# Radio.net
KiCad netlist of a schematic drawn in EAGLE
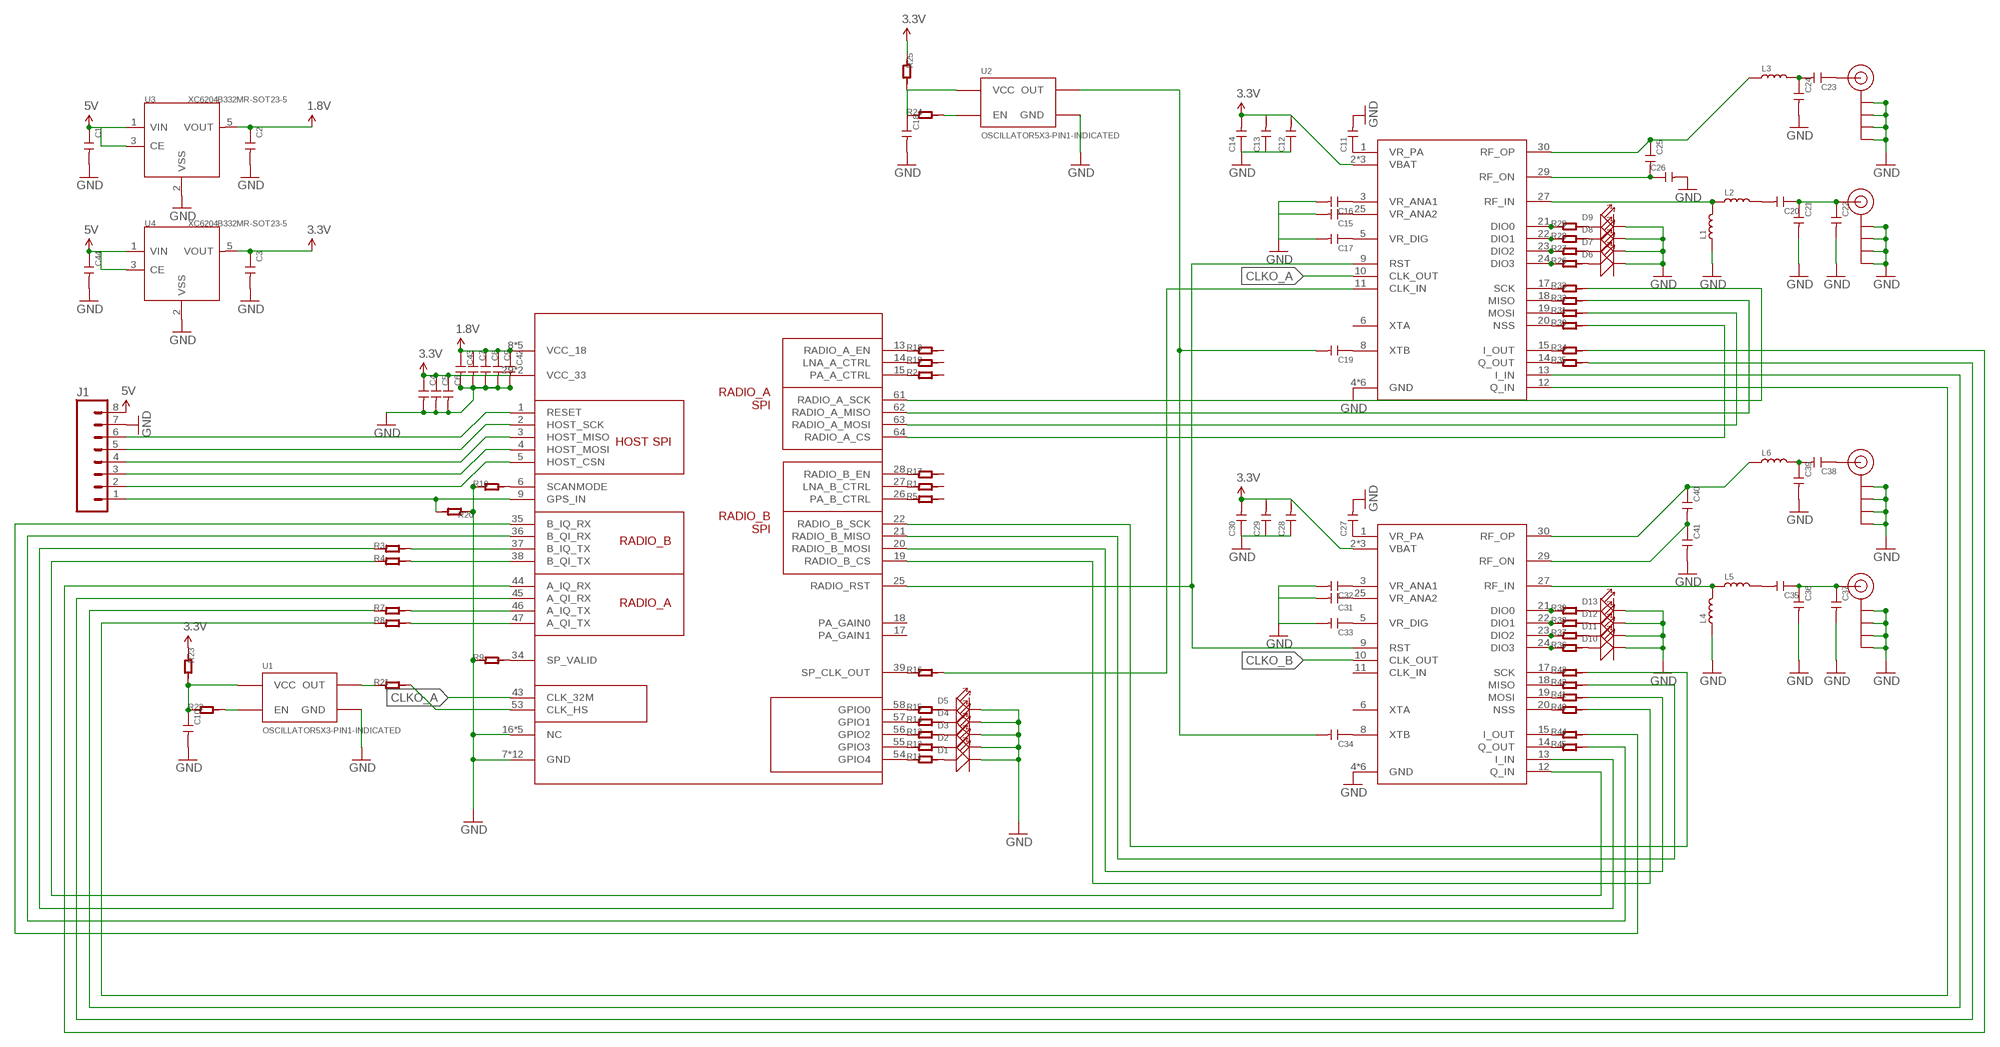
[diagram p0: schematic, sheet 1]

(export (version "E")
  (design (tool "Eeschema 10.0.6"))
  (components
    (comp (ref "C1")
      (value "CAP-0603")
      (footprint "eagle-import:C0603")
      (libsource (lib "eagle-import") (part "CAP-0603"))
    )
    (comp (ref "C2")
      (value "CAP-0402")
      (footprint "eagle-import:C0402")
      (libsource (lib "eagle-import") (part "CAP-0402"))
    )
    (comp (ref "C3")
      (value "CAP-0603")
      (footprint "eagle-import:C0603")
      (libsource (lib "eagle-import") (part "CAP-0603"))
    )
    (comp (ref "C4")
      (value "CAP-0402")
      (footprint "eagle-import:C0402")
      (libsource (lib "eagle-import") (part "CAP-0402"))
    )
    (comp (ref "C5")
      (value "CAP-0805")
      (footprint "eagle-import:C0805")
      (libsource (lib "eagle-import") (part "CAP-0805"))
    )
    (comp (ref "C6")
      (value "CAP-0402")
      (footprint "eagle-import:C0402")
      (libsource (lib "eagle-import") (part "CAP-0402"))
    )
    (comp (ref "C7")
      (value "CAP-0402")
      (footprint "eagle-import:C0402")
      (libsource (lib "eagle-import") (part "CAP-0402"))
    )
    (comp (ref "C8")
      (value "CAP-0402")
      (footprint "eagle-import:C0402")
      (libsource (lib "eagle-import") (part "CAP-0402"))
    )
    (comp (ref "C9")
      (value "CAP-0402")
      (footprint "eagle-import:C0402")
      (libsource (lib "eagle-import") (part "CAP-0402"))
    )
    (comp (ref "C10")
      (value "CAP-0402")
      (footprint "eagle-import:C0402")
      (libsource (lib "eagle-import") (part "CAP-0402"))
    )
    (comp (ref "C11")
      (value "CAP-0402")
      (footprint "eagle-import:C0402")
      (libsource (lib "eagle-import") (part "CAP-0402"))
    )
    (comp (ref "C12")
      (value "CAP-0402")
      (footprint "eagle-import:C0402")
      (libsource (lib "eagle-import") (part "CAP-0402"))
    )
    (comp (ref "C13")
      (value "CAP-0402")
      (footprint "eagle-import:C0402")
      (libsource (lib "eagle-import") (part "CAP-0402"))
    )
    (comp (ref "C14")
      (value "CAP-0402")
      (footprint "eagle-import:C0402")
      (libsource (lib "eagle-import") (part "CAP-0402"))
    )
    (comp (ref "C15")
      (value "CAP-0402")
      (footprint "eagle-import:C0402")
      (libsource (lib "eagle-import") (part "CAP-0402"))
    )
    (comp (ref "C16")
      (value "CAP-0402")
      (footprint "eagle-import:C0402")
      (libsource (lib "eagle-import") (part "CAP-0402"))
    )
    (comp (ref "C17")
      (value "CAP-0402")
      (footprint "eagle-import:C0402")
      (libsource (lib "eagle-import") (part "CAP-0402"))
    )
    (comp (ref "C18")
      (value "CAP-0402")
      (footprint "eagle-import:C0402")
      (libsource (lib "eagle-import") (part "CAP-0402"))
    )
    (comp (ref "C19")
      (value "CAP-0402")
      (footprint "eagle-import:C0402")
      (libsource (lib "eagle-import") (part "CAP-0402"))
    )
    (comp (ref "C20")
      (value "CAP-0402")
      (footprint "eagle-import:C0402")
      (libsource (lib "eagle-import") (part "CAP-0402"))
    )
    (comp (ref "C21")
      (value "CAP-0402")
      (footprint "eagle-import:C0402")
      (libsource (lib "eagle-import") (part "CAP-0402"))
    )
    (comp (ref "C22")
      (value "CAP-0402")
      (footprint "eagle-import:C0402")
      (libsource (lib "eagle-import") (part "CAP-0402"))
    )
    (comp (ref "C23")
      (value "CAP-0402")
      (footprint "eagle-import:C0402")
      (libsource (lib "eagle-import") (part "CAP-0402"))
    )
    (comp (ref "C24")
      (value "CAP-0402")
      (footprint "eagle-import:C0402")
      (libsource (lib "eagle-import") (part "CAP-0402"))
    )
    (comp (ref "C25")
      (value "CAP-0402")
      (footprint "eagle-import:C0402")
      (libsource (lib "eagle-import") (part "CAP-0402"))
    )
    (comp (ref "C26")
      (value "CAP-0402")
      (footprint "eagle-import:C0402")
      (libsource (lib "eagle-import") (part "CAP-0402"))
    )
    (comp (ref "C27")
      (value "CAP-0402")
      (footprint "eagle-import:C0402")
      (libsource (lib "eagle-import") (part "CAP-0402"))
    )
    (comp (ref "C28")
      (value "CAP-0402")
      (footprint "eagle-import:C0402")
      (libsource (lib "eagle-import") (part "CAP-0402"))
    )
    (comp (ref "C29")
      (value "CAP-0402")
      (footprint "eagle-import:C0402")
      (libsource (lib "eagle-import") (part "CAP-0402"))
    )
    (comp (ref "C30")
      (value "CAP-0402")
      (footprint "eagle-import:C0402")
      (libsource (lib "eagle-import") (part "CAP-0402"))
    )
    (comp (ref "C31")
      (value "CAP-0402")
      (footprint "eagle-import:C0402")
      (libsource (lib "eagle-import") (part "CAP-0402"))
    )
    (comp (ref "C32")
      (value "CAP-0402")
      (footprint "eagle-import:C0402")
      (libsource (lib "eagle-import") (part "CAP-0402"))
    )
    (comp (ref "C33")
      (value "CAP-0402")
      (footprint "eagle-import:C0402")
      (libsource (lib "eagle-import") (part "CAP-0402"))
    )
    (comp (ref "C34")
      (value "CAP-0402")
      (footprint "eagle-import:C0402")
      (libsource (lib "eagle-import") (part "CAP-0402"))
    )
    (comp (ref "C35")
      (value "CAP-0402")
      (footprint "eagle-import:C0402")
      (libsource (lib "eagle-import") (part "CAP-0402"))
    )
    (comp (ref "C36")
      (value "CAP-0402")
      (footprint "eagle-import:C0402")
      (libsource (lib "eagle-import") (part "CAP-0402"))
    )
    (comp (ref "C37")
      (value "CAP-0402")
      (footprint "eagle-import:C0402")
      (libsource (lib "eagle-import") (part "CAP-0402"))
    )
    (comp (ref "C38")
      (value "CAP-0402")
      (footprint "eagle-import:C0402")
      (libsource (lib "eagle-import") (part "CAP-0402"))
    )
    (comp (ref "C39")
      (value "CAP-0402")
      (footprint "eagle-import:C0402")
      (libsource (lib "eagle-import") (part "CAP-0402"))
    )
    (comp (ref "C40")
      (value "CAP-0402")
      (footprint "eagle-import:C0402")
      (libsource (lib "eagle-import") (part "CAP-0402"))
    )
    (comp (ref "C41")
      (value "CAP-0402")
      (footprint "eagle-import:C0402")
      (libsource (lib "eagle-import") (part "CAP-0402"))
    )
    (comp (ref "C42")
      (value "CAP-0402")
      (footprint "eagle-import:C0402")
      (libsource (lib "eagle-import") (part "CAP-0402"))
    )
    (comp (ref "C43")
      (value "CAP-0402")
      (footprint "eagle-import:C0402")
      (libsource (lib "eagle-import") (part "CAP-0402"))
    )
    (comp (ref "C44")
      (value "CAP-0402")
      (footprint "eagle-import:C0402")
      (libsource (lib "eagle-import") (part "CAP-0402"))
    )
    (comp (ref "D1")
      (value "LED-0402")
      (footprint "eagle-import:LED-0402")
      (libsource (lib "eagle-import") (part "LED-0402"))
    )
    (comp (ref "D2")
      (value "LED-0402")
      (footprint "eagle-import:LED-0402")
      (libsource (lib "eagle-import") (part "LED-0402"))
    )
    (comp (ref "D3")
      (value "LED-0402")
      (footprint "eagle-import:LED-0402")
      (libsource (lib "eagle-import") (part "LED-0402"))
    )
    (comp (ref "D4")
      (value "LED-0402")
      (footprint "eagle-import:LED-0402")
      (libsource (lib "eagle-import") (part "LED-0402"))
    )
    (comp (ref "D5")
      (value "LED-0402")
      (footprint "eagle-import:LED-0402")
      (libsource (lib "eagle-import") (part "LED-0402"))
    )
    (comp (ref "D6")
      (value "LED-0402")
      (footprint "eagle-import:LED-0402")
      (libsource (lib "eagle-import") (part "LED-0402"))
    )
    (comp (ref "D7")
      (value "LED-0402")
      (footprint "eagle-import:LED-0402")
      (libsource (lib "eagle-import") (part "LED-0402"))
    )
    (comp (ref "D8")
      (value "LED-0402")
      (footprint "eagle-import:LED-0402")
      (libsource (lib "eagle-import") (part "LED-0402"))
    )
    (comp (ref "D9")
      (value "LED-0402")
      (footprint "eagle-import:LED-0402")
      (libsource (lib "eagle-import") (part "LED-0402"))
    )
    (comp (ref "D10")
      (value "LED-0402")
      (footprint "eagle-import:LED-0402")
      (libsource (lib "eagle-import") (part "LED-0402"))
    )
    (comp (ref "D11")
      (value "LED-0402")
      (footprint "eagle-import:LED-0402")
      (libsource (lib "eagle-import") (part "LED-0402"))
    )
    (comp (ref "D12")
      (value "LED-0402")
      (footprint "eagle-import:LED-0402")
      (libsource (lib "eagle-import") (part "LED-0402"))
    )
    (comp (ref "D13")
      (value "LED-0402")
      (footprint "eagle-import:LED-0402")
      (libsource (lib "eagle-import") (part "LED-0402"))
    )
    (comp (ref "J$1")
      (value "SMA_EDGE")
      (footprint "eagle-import:SMA-EDGE")
      (libsource (lib "eagle-import") (part "SMA_EDGE"))
    )
    (comp (ref "J$2")
      (value "SMA_EDGE")
      (footprint "eagle-import:SMA-EDGE")
      (libsource (lib "eagle-import") (part "SMA_EDGE"))
    )
    (comp (ref "J$3")
      (value "SMA_EDGE")
      (footprint "eagle-import:SMA-EDGE")
      (libsource (lib "eagle-import") (part "SMA_EDGE"))
    )
    (comp (ref "J$4")
      (value "SMA_EDGE")
      (footprint "eagle-import:SMA-EDGE")
      (libsource (lib "eagle-import") (part "SMA_EDGE"))
    )
    (comp (ref "J1")
      (value "M08LOCK")
      (footprint "eagle-import:1X08_LOCK")
      (libsource (lib "eagle-import") (part "M08LOCK"))
    )
    (comp (ref "L1")
      (value "INDUCTOR/FERRITE-BEAD-0402")
      (footprint "eagle-import:L0402")
      (libsource (lib "eagle-import") (part "INDUCTOR/FERRITE-BEAD-0402"))
    )
    (comp (ref "L2")
      (value "INDUCTOR/FERRITE-BEAD-0402")
      (footprint "eagle-import:L0402")
      (libsource (lib "eagle-import") (part "INDUCTOR/FERRITE-BEAD-0402"))
    )
    (comp (ref "L3")
      (value "INDUCTOR/FERRITE-BEAD-0402")
      (footprint "eagle-import:L0402")
      (libsource (lib "eagle-import") (part "INDUCTOR/FERRITE-BEAD-0402"))
    )
    (comp (ref "L4")
      (value "INDUCTOR/FERRITE-BEAD-0402")
      (footprint "eagle-import:L0402")
      (libsource (lib "eagle-import") (part "INDUCTOR/FERRITE-BEAD-0402"))
    )
    (comp (ref "L5")
      (value "INDUCTOR/FERRITE-BEAD-0402")
      (footprint "eagle-import:L0402")
      (libsource (lib "eagle-import") (part "INDUCTOR/FERRITE-BEAD-0402"))
    )
    (comp (ref "L6")
      (value "INDUCTOR/FERRITE-BEAD-0402")
      (footprint "eagle-import:L0402")
      (libsource (lib "eagle-import") (part "INDUCTOR/FERRITE-BEAD-0402"))
    )
    (comp (ref "R1")
      (value "R-0402")
      (footprint "eagle-import:R0402")
      (libsource (lib "eagle-import") (part "R-0402"))
    )
    (comp (ref "R2")
      (value "R-0402")
      (footprint "eagle-import:R0402")
      (libsource (lib "eagle-import") (part "R-0402"))
    )
    (comp (ref "R3")
      (value "R-0402")
      (footprint "eagle-import:R0402")
      (libsource (lib "eagle-import") (part "R-0402"))
    )
    (comp (ref "R4")
      (value "R-0402")
      (footprint "eagle-import:R0402")
      (libsource (lib "eagle-import") (part "R-0402"))
    )
    (comp (ref "R5")
      (value "R-0402")
      (footprint "eagle-import:R0402")
      (libsource (lib "eagle-import") (part "R-0402"))
    )
    (comp (ref "R7")
      (value "R-0402")
      (footprint "eagle-import:R0402")
      (libsource (lib "eagle-import") (part "R-0402"))
    )
    (comp (ref "R8")
      (value "R-0402")
      (footprint "eagle-import:R0402")
      (libsource (lib "eagle-import") (part "R-0402"))
    )
    (comp (ref "R9")
      (value "R-0402")
      (footprint "eagle-import:R0402")
      (libsource (lib "eagle-import") (part "R-0402"))
    )
    (comp (ref "R10")
      (value "R-0402")
      (footprint "eagle-import:R0402")
      (libsource (lib "eagle-import") (part "R-0402"))
    )
    (comp (ref "R11")
      (value "R-0402")
      (footprint "eagle-import:R0402")
      (libsource (lib "eagle-import") (part "R-0402"))
    )
    (comp (ref "R12")
      (value "R-0402")
      (footprint "eagle-import:R0402")
      (libsource (lib "eagle-import") (part "R-0402"))
    )
    (comp (ref "R13")
      (value "R-0402")
      (footprint "eagle-import:R0402")
      (libsource (lib "eagle-import") (part "R-0402"))
    )
    (comp (ref "R14")
      (value "R-0402")
      (footprint "eagle-import:R0402")
      (libsource (lib "eagle-import") (part "R-0402"))
    )
    (comp (ref "R15")
      (value "R-0402")
      (footprint "eagle-import:R0402")
      (libsource (lib "eagle-import") (part "R-0402"))
    )
    (comp (ref "R16")
      (value "R-0402")
      (footprint "eagle-import:R0402")
      (libsource (lib "eagle-import") (part "R-0402"))
    )
    (comp (ref "R17")
      (value "R-0402")
      (footprint "eagle-import:R0402")
      (libsource (lib "eagle-import") (part "R-0402"))
    )
    (comp (ref "R18")
      (value "R-0402")
      (footprint "eagle-import:R0402")
      (libsource (lib "eagle-import") (part "R-0402"))
    )
    (comp (ref "R19")
      (value "R-0402")
      (footprint "eagle-import:R0402")
      (libsource (lib "eagle-import") (part "R-0402"))
    )
    (comp (ref "R20")
      (value "R-0402")
      (footprint "eagle-import:R0402")
      (libsource (lib "eagle-import") (part "R-0402"))
    )
    (comp (ref "R21")
      (value "R-0402")
      (footprint "eagle-import:R0402")
      (libsource (lib "eagle-import") (part "R-0402"))
    )
    (comp (ref "R22")
      (value "R-0402")
      (footprint "eagle-import:R0402")
      (libsource (lib "eagle-import") (part "R-0402"))
    )
    (comp (ref "R23")
      (value "R-0402")
      (footprint "eagle-import:R0402")
      (libsource (lib "eagle-import") (part "R-0402"))
    )
    (comp (ref "R24")
      (value "R-0402")
      (footprint "eagle-import:R0402")
      (libsource (lib "eagle-import") (part "R-0402"))
    )
    (comp (ref "R25")
      (value "R-0402")
      (footprint "eagle-import:R0402")
      (libsource (lib "eagle-import") (part "R-0402"))
    )
    (comp (ref "R26")
      (value "R-0402")
      (footprint "eagle-import:R0402")
      (libsource (lib "eagle-import") (part "R-0402"))
    )
    (comp (ref "R27")
      (value "R-0402")
      (footprint "eagle-import:R0402")
      (libsource (lib "eagle-import") (part "R-0402"))
    )
    (comp (ref "R28")
      (value "R-0402")
      (footprint "eagle-import:R0402")
      (libsource (lib "eagle-import") (part "R-0402"))
    )
    (comp (ref "R29")
      (value "R-0402")
      (footprint "eagle-import:R0402")
      (libsource (lib "eagle-import") (part "R-0402"))
    )
    (comp (ref "R30")
      (value "R-0402")
      (footprint "eagle-import:R0402")
      (libsource (lib "eagle-import") (part "R-0402"))
    )
    (comp (ref "R31")
      (value "R-0402")
      (footprint "eagle-import:R0402")
      (libsource (lib "eagle-import") (part "R-0402"))
    )
    (comp (ref "R32")
      (value "R-0402")
      (footprint "eagle-import:R0402")
      (libsource (lib "eagle-import") (part "R-0402"))
    )
    (comp (ref "R33")
      (value "R-0402")
      (footprint "eagle-import:R0402")
      (libsource (lib "eagle-import") (part "R-0402"))
    )
    (comp (ref "R34")
      (value "R-0402")
      (footprint "eagle-import:R0402")
      (libsource (lib "eagle-import") (part "R-0402"))
    )
    (comp (ref "R35")
      (value "R-0402")
      (footprint "eagle-import:R0402")
      (libsource (lib "eagle-import") (part "R-0402"))
    )
    (comp (ref "R36")
      (value "R-0402")
      (footprint "eagle-import:R0402")
      (libsource (lib "eagle-import") (part "R-0402"))
    )
    (comp (ref "R37")
      (value "R-0402")
      (footprint "eagle-import:R0402")
      (libsource (lib "eagle-import") (part "R-0402"))
    )
    (comp (ref "R38")
      (value "R-0402")
      (footprint "eagle-import:R0402")
      (libsource (lib "eagle-import") (part "R-0402"))
    )
    (comp (ref "R39")
      (value "R-0402")
      (footprint "eagle-import:R0402")
      (libsource (lib "eagle-import") (part "R-0402"))
    )
    (comp (ref "R40")
      (value "R-0402")
      (footprint "eagle-import:R0402")
      (libsource (lib "eagle-import") (part "R-0402"))
    )
    (comp (ref "R41")
      (value "R-0402")
      (footprint "eagle-import:R0402")
      (libsource (lib "eagle-import") (part "R-0402"))
    )
    (comp (ref "R42")
      (value "R-0402")
      (footprint "eagle-import:R0402")
      (libsource (lib "eagle-import") (part "R-0402"))
    )
    (comp (ref "R43")
      (value "R-0402")
      (footprint "eagle-import:R0402")
      (libsource (lib "eagle-import") (part "R-0402"))
    )
    (comp (ref "R44")
      (value "R-0402")
      (footprint "eagle-import:R0402")
      (libsource (lib "eagle-import") (part "R-0402"))
    )
    (comp (ref "R45")
      (value "R-0402")
      (footprint "eagle-import:R0402")
      (libsource (lib "eagle-import") (part "R-0402"))
    )
    (comp (ref "U$1")
      (value "SX1301")
      (footprint "eagle-import:QFN64G-0.5-9X9MM")
      (libsource (lib "eagle-import") (part "SX1301"))
    )
    (comp (ref "U$2")
      (value "SX1255")
      (footprint "eagle-import:QFN32G-0.5-5X5MM")
      (libsource (lib "eagle-import") (part "SX1255"))
    )
    (comp (ref "U$3")
      (value "SX1255")
      (footprint "eagle-import:QFN32G-0.5-5X5MM")
      (libsource (lib "eagle-import") (part "SX1255"))
    )
    (comp (ref "U1")
      (value "OSCILLATOR5X3-PIN1-INDICATED")
      (footprint "eagle-import:CRYSTAL-OSC-SMD-5X3")
      (libsource (lib "eagle-import") (part "OSCILLATOR5X3-PIN1-INDICATED"))
    )
    (comp (ref "U2")
      (value "OSCILLATOR5X3-PIN1-INDICATED")
      (footprint "eagle-import:CRYSTAL-OSC-SMD-5X3")
      (libsource (lib "eagle-import") (part "OSCILLATOR5X3-PIN1-INDICATED"))
    )
    (comp (ref "U3")
      (value "XC6204B332MR-SOT23-5")
      (footprint "eagle-import:SOT-23-5")
      (fields (field (name "MPN") "XC6204B332MR"))
      (libsource (lib "eagle-import") (part "PMIC-XC6204B332MR(SOT23-5)"))
    )
    (comp (ref "U4")
      (value "XC6204B332MR-SOT23-5")
      (footprint "eagle-import:SOT-23-5")
      (fields (field (name "MPN") "XC6204B332MR"))
      (libsource (lib "eagle-import") (part "PMIC-XC6204B332MR(SOT23-5)"))
    )
  )
  (nets
    (net (code "1") (name "1.8V") (class "Default")
      (node (ref "C2") (pin "1") (pinfunction "1_1") (pintype "passive"))
      (node (ref "C42") (pin "1") (pinfunction "1_1") (pintype "passive"))
      (node (ref "C43") (pin "1") (pinfunction "1_1") (pintype "passive"))
      (node (ref "C7") (pin "1") (pinfunction "1_1") (pintype "passive"))
      (node (ref "C8") (pin "1") (pinfunction "1_1") (pintype "passive"))
      (node (ref "C9") (pin "1") (pinfunction "1_1") (pintype "passive"))
      (node (ref "U$1") (pin "12") (pinfunction "VCC_18_12") (pintype "bidirectional"))
      (node (ref "U$1") (pin "23") (pinfunction "VCC_18_23") (pintype "bidirectional"))
      (node (ref "U$1") (pin "42") (pinfunction "VCC_18_42") (pintype "bidirectional"))
      (node (ref "U$1") (pin "60") (pinfunction "VCC_18_60") (pintype "bidirectional"))
      (node (ref "U$1") (pin "8") (pinfunction "VCC_18_8") (pintype "bidirectional"))
      (node (ref "U3") (pin "5") (pinfunction "VOUT_5") (pintype "bidirectional"))
    )
    (net (code "2") (name "3.3V") (class "Default")
      (node (ref "C12") (pin "2") (pinfunction "2_2") (pintype "passive"))
      (node (ref "C13") (pin "2") (pinfunction "2_2") (pintype "passive"))
      (node (ref "C14") (pin "2") (pinfunction "2_2") (pintype "passive"))
      (node (ref "C28") (pin "2") (pinfunction "2_2") (pintype "passive"))
      (node (ref "C29") (pin "2") (pinfunction "2_2") (pintype "passive"))
      (node (ref "C3") (pin "1") (pinfunction "1_1") (pintype "passive"))
      (node (ref "C30") (pin "2") (pinfunction "2_2") (pintype "passive"))
      (node (ref "C4") (pin "1") (pinfunction "1_1") (pintype "passive"))
      (node (ref "C5") (pin "1") (pinfunction "1_1") (pintype "passive"))
      (node (ref "C6") (pin "1") (pinfunction "1_1") (pintype "passive"))
      (node (ref "R23") (pin "1") (pinfunction "1_1") (pintype "bidirectional"))
      (node (ref "R25") (pin "1") (pinfunction "1_1") (pintype "bidirectional"))
      (node (ref "U$1") (pin "29") (pinfunction "VCC_33_29") (pintype "bidirectional"))
      (node (ref "U$1") (pin "52") (pinfunction "VCC_33_52") (pintype "bidirectional"))
      (node (ref "U$2") (pin "16") (pinfunction "VBAT_16") (pintype "bidirectional"))
      (node (ref "U$2") (pin "2") (pinfunction "VBAT_2") (pintype "bidirectional"))
      (node (ref "U$2") (pin "32") (pinfunction "VBAT_32") (pintype "bidirectional"))
      (node (ref "U$3") (pin "16") (pinfunction "VBAT_16") (pintype "bidirectional"))
      (node (ref "U$3") (pin "2") (pinfunction "VBAT_2") (pintype "bidirectional"))
      (node (ref "U$3") (pin "32") (pinfunction "VBAT_32") (pintype "bidirectional"))
      (node (ref "U4") (pin "5") (pinfunction "VOUT_5") (pintype "bidirectional"))
    )
    (net (code "3") (name "5V") (class "Default")
      (node (ref "C1") (pin "1") (pinfunction "1_1") (pintype "passive"))
      (node (ref "C44") (pin "1") (pinfunction "1_1") (pintype "passive"))
      (node (ref "J1") (pin "8") (pinfunction "8_8") (pintype "passive"))
      (node (ref "U3") (pin "1") (pinfunction "VIN_1") (pintype "bidirectional"))
      (node (ref "U3") (pin "3") (pinfunction "CE_3") (pintype "bidirectional"))
      (node (ref "U4") (pin "1") (pinfunction "VIN_1") (pintype "bidirectional"))
      (node (ref "U4") (pin "3") (pinfunction "CE_3") (pintype "bidirectional"))
    )
    (net (code "4") (name "CLKO_A") (class "Default")
      (node (ref "U$1") (pin "43") (pinfunction "CLK_32M_43") (pintype "bidirectional"))
      (node (ref "U$2") (pin "10") (pinfunction "CLK_OUT_10") (pintype "bidirectional"))
    )
    (net (code "5") (name "CLKO_B") (class "Default")
      (node (ref "U$3") (pin "10") (pinfunction "CLK_OUT_10") (pintype "bidirectional"))
    )
    (net (code "6") (name "GND") (class "Default")
      (node (ref "C1") (pin "2") (pinfunction "2_2") (pintype "passive"))
      (node (ref "C10") (pin "2") (pinfunction "2_2") (pintype "passive"))
      (node (ref "C11") (pin "2") (pinfunction "2_2") (pintype "passive"))
      (node (ref "C12") (pin "1") (pinfunction "1_1") (pintype "passive"))
      (node (ref "C13") (pin "1") (pinfunction "1_1") (pintype "passive"))
      (node (ref "C14") (pin "1") (pinfunction "1_1") (pintype "passive"))
      (node (ref "C15") (pin "2") (pinfunction "2_2") (pintype "passive"))
      (node (ref "C16") (pin "2") (pinfunction "2_2") (pintype "passive"))
      (node (ref "C17") (pin "2") (pinfunction "2_2") (pintype "passive"))
      (node (ref "C18") (pin "2") (pinfunction "2_2") (pintype "passive"))
      (node (ref "C2") (pin "2") (pinfunction "2_2") (pintype "passive"))
      (node (ref "C21") (pin "2") (pinfunction "2_2") (pintype "passive"))
      (node (ref "C22") (pin "2") (pinfunction "2_2") (pintype "passive"))
      (node (ref "C24") (pin "2") (pinfunction "2_2") (pintype "passive"))
      (node (ref "C26") (pin "2") (pinfunction "2_2") (pintype "passive"))
      (node (ref "C27") (pin "2") (pinfunction "2_2") (pintype "passive"))
      (node (ref "C28") (pin "1") (pinfunction "1_1") (pintype "passive"))
      (node (ref "C29") (pin "1") (pinfunction "1_1") (pintype "passive"))
      (node (ref "C3") (pin "2") (pinfunction "2_2") (pintype "passive"))
      (node (ref "C30") (pin "1") (pinfunction "1_1") (pintype "passive"))
      (node (ref "C31") (pin "2") (pinfunction "2_2") (pintype "passive"))
      (node (ref "C32") (pin "2") (pinfunction "2_2") (pintype "passive"))
      (node (ref "C33") (pin "2") (pinfunction "2_2") (pintype "passive"))
      (node (ref "C36") (pin "2") (pinfunction "2_2") (pintype "passive"))
      (node (ref "C37") (pin "2") (pinfunction "2_2") (pintype "passive"))
      (node (ref "C39") (pin "2") (pinfunction "2_2") (pintype "passive"))
      (node (ref "C4") (pin "2") (pinfunction "2_2") (pintype "passive"))
      (node (ref "C41") (pin "2") (pinfunction "2_2") (pintype "passive"))
      (node (ref "C42") (pin "2") (pinfunction "2_2") (pintype "passive"))
      (node (ref "C43") (pin "2") (pinfunction "2_2") (pintype "passive"))
      (node (ref "C44") (pin "2") (pinfunction "2_2") (pintype "passive"))
      (node (ref "C5") (pin "2") (pinfunction "2_2") (pintype "passive"))
      (node (ref "C6") (pin "2") (pinfunction "2_2") (pintype "passive"))
      (node (ref "C7") (pin "2") (pinfunction "2_2") (pintype "passive"))
      (node (ref "C8") (pin "2") (pinfunction "2_2") (pintype "passive"))
      (node (ref "C9") (pin "2") (pinfunction "2_2") (pintype "passive"))
      (node (ref "D1") (pin "-") (pinfunction "-_-") (pintype "passive"))
      (node (ref "D10") (pin "-") (pinfunction "-_-") (pintype "passive"))
      (node (ref "D11") (pin "-") (pinfunction "-_-") (pintype "passive"))
      (node (ref "D12") (pin "-") (pinfunction "-_-") (pintype "passive"))
      (node (ref "D13") (pin "-") (pinfunction "-_-") (pintype "passive"))
      (node (ref "D2") (pin "-") (pinfunction "-_-") (pintype "passive"))
      (node (ref "D3") (pin "-") (pinfunction "-_-") (pintype "passive"))
      (node (ref "D4") (pin "-") (pinfunction "-_-") (pintype "passive"))
      (node (ref "D5") (pin "-") (pinfunction "-_-") (pintype "passive"))
      (node (ref "D6") (pin "-") (pinfunction "-_-") (pintype "passive"))
      (node (ref "D7") (pin "-") (pinfunction "-_-") (pintype "passive"))
      (node (ref "D8") (pin "-") (pinfunction "-_-") (pintype "passive"))
      (node (ref "D9") (pin "-") (pinfunction "-_-") (pintype "passive"))
      (node (ref "J$1") (pin "GND@0") (pinfunction "GND_GND@0") (pintype "bidirectional"))
      (node (ref "J$1") (pin "GND@1") (pinfunction "GND_GND@1") (pintype "bidirectional"))
      (node (ref "J$1") (pin "GND@2") (pinfunction "GND_GND@2") (pintype "bidirectional"))
      (node (ref "J$1") (pin "GND@3") (pinfunction "GND_GND@3") (pintype "bidirectional"))
      (node (ref "J$2") (pin "GND@0") (pinfunction "GND_GND@0") (pintype "bidirectional"))
      (node (ref "J$2") (pin "GND@1") (pinfunction "GND_GND@1") (pintype "bidirectional"))
      (node (ref "J$2") (pin "GND@2") (pinfunction "GND_GND@2") (pintype "bidirectional"))
      (node (ref "J$2") (pin "GND@3") (pinfunction "GND_GND@3") (pintype "bidirectional"))
      (node (ref "J$3") (pin "GND@0") (pinfunction "GND_GND@0") (pintype "bidirectional"))
      (node (ref "J$3") (pin "GND@1") (pinfunction "GND_GND@1") (pintype "bidirectional"))
      (node (ref "J$3") (pin "GND@2") (pinfunction "GND_GND@2") (pintype "bidirectional"))
      (node (ref "J$3") (pin "GND@3") (pinfunction "GND_GND@3") (pintype "bidirectional"))
      (node (ref "J$4") (pin "GND@0") (pinfunction "GND_GND@0") (pintype "bidirectional"))
      (node (ref "J$4") (pin "GND@1") (pinfunction "GND_GND@1") (pintype "bidirectional"))
      (node (ref "J$4") (pin "GND@2") (pinfunction "GND_GND@2") (pintype "bidirectional"))
      (node (ref "J$4") (pin "GND@3") (pinfunction "GND_GND@3") (pintype "bidirectional"))
      (node (ref "J1") (pin "7") (pinfunction "7_7") (pintype "passive"))
      (node (ref "L1") (pin "1") (pinfunction "1_1") (pintype "passive"))
      (node (ref "L4") (pin "1") (pinfunction "1_1") (pintype "passive"))
      (node (ref "R10") (pin "1") (pinfunction "1_1") (pintype "bidirectional"))
      (node (ref "R20") (pin "1") (pinfunction "1_1") (pintype "bidirectional"))
      (node (ref "R9") (pin "1") (pinfunction "1_1") (pintype "bidirectional"))
      (node (ref "U$1") (pin "10") (pinfunction "GND_10") (pintype "bidirectional"))
      (node (ref "U$1") (pin "11") (pinfunction "GND_11") (pintype "bidirectional"))
      (node (ref "U$1") (pin "16") (pinfunction "NC_16") (pintype "bidirectional"))
      (node (ref "U$1") (pin "24") (pinfunction "GND_24") (pintype "bidirectional"))
      (node (ref "U$1") (pin "30") (pinfunction "GND_30") (pintype "bidirectional"))
      (node (ref "U$1") (pin "31") (pinfunction "GND_31") (pintype "bidirectional"))
      (node (ref "U$1") (pin "32") (pinfunction "NC_32") (pintype "bidirectional"))
      (node (ref "U$1") (pin "33") (pinfunction "NC_33") (pintype "bidirectional"))
      (node (ref "U$1") (pin "40") (pinfunction "GND_40") (pintype "bidirectional"))
      (node (ref "U$1") (pin "41") (pinfunction "GND_41") (pintype "bidirectional"))
      (node (ref "U$1") (pin "48") (pinfunction "NC_48") (pintype "bidirectional"))
      (node (ref "U$1") (pin "49") (pinfunction "NC_49") (pintype "bidirectional"))
      (node (ref "U$1") (pin "50") (pinfunction "GND_50") (pintype "bidirectional"))
      (node (ref "U$1") (pin "51") (pinfunction "GND_51") (pintype "bidirectional"))
      (node (ref "U$1") (pin "59") (pinfunction "GND_59") (pintype "bidirectional"))
      (node (ref "U$1") (pin "65") (pinfunction "GND_65") (pintype "bidirectional"))
      (node (ref "U$1") (pin "7") (pinfunction "GND_7") (pintype "bidirectional"))
      (node (ref "U$2") (pin "26") (pinfunction "GND_26") (pintype "bidirectional"))
      (node (ref "U$2") (pin "28") (pinfunction "GND_28") (pintype "bidirectional"))
      (node (ref "U$2") (pin "31") (pinfunction "GND_31") (pintype "bidirectional"))
      (node (ref "U$2") (pin "33") (pinfunction "GND_33") (pintype "bidirectional"))
      (node (ref "U$2") (pin "4") (pinfunction "GND_4") (pintype "bidirectional"))
      (node (ref "U$2") (pin "7") (pinfunction "GND_7") (pintype "bidirectional"))
      (node (ref "U$3") (pin "26") (pinfunction "GND_26") (pintype "bidirectional"))
      (node (ref "U$3") (pin "28") (pinfunction "GND_28") (pintype "bidirectional"))
      (node (ref "U$3") (pin "31") (pinfunction "GND_31") (pintype "bidirectional"))
      (node (ref "U$3") (pin "33") (pinfunction "GND_33") (pintype "bidirectional"))
      (node (ref "U$3") (pin "4") (pinfunction "GND_4") (pintype "bidirectional"))
      (node (ref "U$3") (pin "7") (pinfunction "GND_7") (pintype "bidirectional"))
      (node (ref "U1") (pin "2") (pinfunction "GND_2") (pintype "bidirectional"))
      (node (ref "U2") (pin "2") (pinfunction "GND_2") (pintype "bidirectional"))
      (node (ref "U3") (pin "2") (pinfunction "VSS_2") (pintype "bidirectional"))
      (node (ref "U4") (pin "2") (pinfunction "VSS_2") (pintype "bidirectional"))
    )
    (net (code "7") (name "Net-(C20-Pad2)") (class "Default")
      (node (ref "C20") (pin "2") (pinfunction "2_2") (pintype "passive"))
      (node (ref "L2") (pin "2") (pinfunction "2_2") (pintype "passive"))
    )
    (net (code "8") (name "Net-(C23-Pad2)") (class "Default")
      (node (ref "C23") (pin "2") (pinfunction "2_2") (pintype "passive"))
      (node (ref "C24") (pin "1") (pinfunction "1_1") (pintype "passive"))
      (node (ref "L3") (pin "2") (pinfunction "2_2") (pintype "passive"))
    )
    (net (code "9") (name "Net-(C35-Pad2)") (class "Default")
      (node (ref "C35") (pin "2") (pinfunction "2_2") (pintype "passive"))
      (node (ref "L5") (pin "2") (pinfunction "2_2") (pintype "passive"))
    )
    (net (code "10") (name "Net-(C38-Pad2)") (class "Default")
      (node (ref "C38") (pin "2") (pinfunction "2_2") (pintype "passive"))
      (node (ref "C39") (pin "1") (pinfunction "1_1") (pintype "passive"))
      (node (ref "L6") (pin "2") (pinfunction "2_2") (pintype "passive"))
    )
    (net (code "11") (name "Net-(D1-Pad+)") (class "Default")
      (node (ref "D1") (pin "+") (pinfunction "+_+") (pintype "passive"))
      (node (ref "R11") (pin "2") (pinfunction "2_2") (pintype "bidirectional"))
    )
    (net (code "12") (name "Net-(D2-Pad+)") (class "Default")
      (node (ref "D2") (pin "+") (pinfunction "+_+") (pintype "passive"))
      (node (ref "R12") (pin "2") (pinfunction "2_2") (pintype "bidirectional"))
    )
    (net (code "13") (name "Net-(D3-Pad+)") (class "Default")
      (node (ref "D3") (pin "+") (pinfunction "+_+") (pintype "passive"))
      (node (ref "R13") (pin "2") (pinfunction "2_2") (pintype "bidirectional"))
    )
    (net (code "14") (name "Net-(D4-Pad+)") (class "Default")
      (node (ref "D4") (pin "+") (pinfunction "+_+") (pintype "passive"))
      (node (ref "R14") (pin "2") (pinfunction "2_2") (pintype "bidirectional"))
    )
    (net (code "15") (name "Net-(D5-Pad+)") (class "Default")
      (node (ref "D5") (pin "+") (pinfunction "+_+") (pintype "passive"))
      (node (ref "R15") (pin "2") (pinfunction "2_2") (pintype "bidirectional"))
    )
    (net (code "16") (name "Net-(D6-Pad+)") (class "Default")
      (node (ref "D6") (pin "+") (pinfunction "+_+") (pintype "passive"))
      (node (ref "R26") (pin "2") (pinfunction "2_2") (pintype "bidirectional"))
    )
    (net (code "17") (name "Net-(D7-Pad+)") (class "Default")
      (node (ref "D7") (pin "+") (pinfunction "+_+") (pintype "passive"))
      (node (ref "R27") (pin "2") (pinfunction "2_2") (pintype "bidirectional"))
    )
    (net (code "18") (name "Net-(D8-Pad+)") (class "Default")
      (node (ref "D8") (pin "+") (pinfunction "+_+") (pintype "passive"))
      (node (ref "R28") (pin "2") (pinfunction "2_2") (pintype "bidirectional"))
    )
    (net (code "19") (name "Net-(D9-Pad+)") (class "Default")
      (node (ref "D9") (pin "+") (pinfunction "+_+") (pintype "passive"))
      (node (ref "R29") (pin "2") (pinfunction "2_2") (pintype "bidirectional"))
    )
    (net (code "20") (name "Net-(D10-Pad+)") (class "Default")
      (node (ref "D10") (pin "+") (pinfunction "+_+") (pintype "passive"))
      (node (ref "R36") (pin "2") (pinfunction "2_2") (pintype "bidirectional"))
    )
    (net (code "21") (name "Net-(D11-Pad+)") (class "Default")
      (node (ref "D11") (pin "+") (pinfunction "+_+") (pintype "passive"))
      (node (ref "R37") (pin "2") (pinfunction "2_2") (pintype "bidirectional"))
    )
    (net (code "22") (name "Net-(D12-Pad+)") (class "Default")
      (node (ref "D12") (pin "+") (pinfunction "+_+") (pintype "passive"))
      (node (ref "R38") (pin "2") (pinfunction "2_2") (pintype "bidirectional"))
    )
    (net (code "23") (name "Net-(D13-Pad+)") (class "Default")
      (node (ref "D13") (pin "+") (pinfunction "+_+") (pintype "passive"))
      (node (ref "R39") (pin "2") (pinfunction "2_2") (pintype "bidirectional"))
    )
    (net (code "24") (name "Net-(J$1-SIGNAL)") (class "Default")
      (node (ref "C20") (pin "1") (pinfunction "1_1") (pintype "passive"))
      (node (ref "C21") (pin "1") (pinfunction "1_1") (pintype "passive"))
      (node (ref "C22") (pin "1") (pinfunction "1_1") (pintype "passive"))
      (node (ref "J$1") (pin "SIG") (pinfunction "SIGNAL_SIG") (pintype "bidirectional"))
    )
    (net (code "25") (name "Net-(J$2-SIGNAL)") (class "Default")
      (node (ref "C23") (pin "1") (pinfunction "1_1") (pintype "passive"))
      (node (ref "J$2") (pin "SIG") (pinfunction "SIGNAL_SIG") (pintype "bidirectional"))
    )
    (net (code "26") (name "Net-(J$3-SIGNAL)") (class "Default")
      (node (ref "C35") (pin "1") (pinfunction "1_1") (pintype "passive"))
      (node (ref "C36") (pin "1") (pinfunction "1_1") (pintype "passive"))
      (node (ref "C37") (pin "1") (pinfunction "1_1") (pintype "passive"))
      (node (ref "J$3") (pin "SIG") (pinfunction "SIGNAL_SIG") (pintype "bidirectional"))
    )
    (net (code "27") (name "Net-(J$4-SIGNAL)") (class "Default")
      (node (ref "C38") (pin "1") (pinfunction "1_1") (pintype "passive"))
      (node (ref "J$4") (pin "SIG") (pinfunction "SIGNAL_SIG") (pintype "bidirectional"))
    )
    (net (code "28") (name "Net-(U$1-A_IQ_RX)") (class "Default")
      (node (ref "R34") (pin "2") (pinfunction "2_2") (pintype "bidirectional"))
      (node (ref "U$1") (pin "44") (pinfunction "A_IQ_RX_44") (pintype "bidirectional"))
    )
    (net (code "29") (name "Net-(U$1-A_IQ_TX)") (class "Default")
      (node (ref "R7") (pin "2") (pinfunction "2_2") (pintype "bidirectional"))
      (node (ref "U$1") (pin "46") (pinfunction "A_IQ_TX_46") (pintype "bidirectional"))
    )
    (net (code "30") (name "Net-(U$1-A_QI_RX)") (class "Default")
      (node (ref "R35") (pin "2") (pinfunction "2_2") (pintype "bidirectional"))
      (node (ref "U$1") (pin "45") (pinfunction "A_QI_RX_45") (pintype "bidirectional"))
    )
    (net (code "31") (name "Net-(U$1-A_QI_TX)") (class "Default")
      (node (ref "R8") (pin "2") (pinfunction "2_2") (pintype "bidirectional"))
      (node (ref "U$1") (pin "47") (pinfunction "A_QI_TX_47") (pintype "bidirectional"))
    )
    (net (code "32") (name "Net-(U$1-B_IQ_RX)") (class "Default")
      (node (ref "R44") (pin "2") (pinfunction "2_2") (pintype "bidirectional"))
      (node (ref "U$1") (pin "35") (pinfunction "B_IQ_RX_35") (pintype "bidirectional"))
    )
    (net (code "33") (name "Net-(U$1-B_IQ_TX)") (class "Default")
      (node (ref "R3") (pin "2") (pinfunction "2_2") (pintype "bidirectional"))
      (node (ref "U$1") (pin "37") (pinfunction "B_IQ_TX_37") (pintype "bidirectional"))
    )
    (net (code "34") (name "Net-(U$1-B_QI_RX)") (class "Default")
      (node (ref "R45") (pin "2") (pinfunction "2_2") (pintype "bidirectional"))
      (node (ref "U$1") (pin "36") (pinfunction "B_QI_RX_36") (pintype "bidirectional"))
    )
    (net (code "35") (name "Net-(U$1-B_QI_TX)") (class "Default")
      (node (ref "R4") (pin "2") (pinfunction "2_2") (pintype "bidirectional"))
      (node (ref "U$1") (pin "38") (pinfunction "B_QI_TX_38") (pintype "bidirectional"))
    )
    (net (code "36") (name "Net-(U$1-CLK_HS)") (class "Default")
      (node (ref "R21") (pin "2") (pinfunction "2_2") (pintype "bidirectional"))
      (node (ref "U$1") (pin "53") (pinfunction "CLK_HS_53") (pintype "bidirectional"))
    )
    (net (code "37") (name "Net-(U$1-GPIO0)") (class "Default")
      (node (ref "R15") (pin "1") (pinfunction "1_1") (pintype "bidirectional"))
      (node (ref "U$1") (pin "58") (pinfunction "GPIO0_58") (pintype "bidirectional"))
    )
    (net (code "38") (name "Net-(U$1-GPIO1)") (class "Default")
      (node (ref "R14") (pin "1") (pinfunction "1_1") (pintype "bidirectional"))
      (node (ref "U$1") (pin "57") (pinfunction "GPIO1_57") (pintype "bidirectional"))
    )
    (net (code "39") (name "Net-(U$1-GPIO2)") (class "Default")
      (node (ref "R13") (pin "1") (pinfunction "1_1") (pintype "bidirectional"))
      (node (ref "U$1") (pin "56") (pinfunction "GPIO2_56") (pintype "bidirectional"))
    )
    (net (code "40") (name "Net-(U$1-GPIO3)") (class "Default")
      (node (ref "R12") (pin "1") (pinfunction "1_1") (pintype "bidirectional"))
      (node (ref "U$1") (pin "55") (pinfunction "GPIO3_55") (pintype "bidirectional"))
    )
    (net (code "41") (name "Net-(U$1-GPIO4)") (class "Default")
      (node (ref "R11") (pin "1") (pinfunction "1_1") (pintype "bidirectional"))
      (node (ref "U$1") (pin "54") (pinfunction "GPIO4_54") (pintype "bidirectional"))
    )
    (net (code "42") (name "Net-(U$1-GPS_IN)") (class "Default")
      (node (ref "J1") (pin "1") (pinfunction "1_1") (pintype "passive"))
      (node (ref "R20") (pin "2") (pinfunction "2_2") (pintype "bidirectional"))
      (node (ref "U$1") (pin "9") (pinfunction "GPS_IN_9") (pintype "bidirectional"))
    )
    (net (code "43") (name "Net-(U$1-HOST_CSN)") (class "Default")
      (node (ref "J1") (pin "2") (pinfunction "2_2") (pintype "passive"))
      (node (ref "U$1") (pin "5") (pinfunction "HOST_CSN_5") (pintype "bidirectional"))
    )
    (net (code "44") (name "Net-(U$1-HOST_MISO)") (class "Default")
      (node (ref "J1") (pin "4") (pinfunction "4_4") (pintype "passive"))
      (node (ref "U$1") (pin "3") (pinfunction "HOST_MISO_3") (pintype "bidirectional"))
    )
    (net (code "45") (name "Net-(U$1-HOST_MOSI)") (class "Default")
      (node (ref "J1") (pin "3") (pinfunction "3_3") (pintype "passive"))
      (node (ref "U$1") (pin "4") (pinfunction "HOST_MOSI_4") (pintype "bidirectional"))
    )
    (net (code "46") (name "Net-(U$1-HOST_SCK)") (class "Default")
      (node (ref "J1") (pin "5") (pinfunction "5_5") (pintype "passive"))
      (node (ref "U$1") (pin "2") (pinfunction "HOST_SCK_2") (pintype "bidirectional"))
    )
    (net (code "47") (name "Net-(U$1-LNA_A_CTRL)") (class "Default")
      (node (ref "R19") (pin "1") (pinfunction "1_1") (pintype "bidirectional"))
      (node (ref "U$1") (pin "14") (pinfunction "LNA_A_CTRL_14") (pintype "bidirectional"))
    )
    (net (code "48") (name "Net-(U$1-LNA_B_CTRL)") (class "Default")
      (node (ref "R1") (pin "1") (pinfunction "1_1") (pintype "bidirectional"))
      (node (ref "U$1") (pin "27") (pinfunction "LNA_B_CTRL_27") (pintype "bidirectional"))
    )
    (net (code "49") (name "Net-(U$1-PA_A_CTRL)") (class "Default")
      (node (ref "R2") (pin "1") (pinfunction "1_1") (pintype "bidirectional"))
      (node (ref "U$1") (pin "15") (pinfunction "PA_A_CTRL_15") (pintype "bidirectional"))
    )
    (net (code "50") (name "Net-(U$1-PA_B_CTRL)") (class "Default")
      (node (ref "R5") (pin "1") (pinfunction "1_1") (pintype "bidirectional"))
      (node (ref "U$1") (pin "26") (pinfunction "PA_B_CTRL_26") (pintype "bidirectional"))
    )
    (net (code "51") (name "Net-(U$1-RADIO_A_CS)") (class "Default")
      (node (ref "R30") (pin "2") (pinfunction "2_2") (pintype "bidirectional"))
      (node (ref "U$1") (pin "64") (pinfunction "RADIO_A_CS_64") (pintype "bidirectional"))
    )
    (net (code "52") (name "Net-(U$1-RADIO_A_EN)") (class "Default")
      (node (ref "R18") (pin "1") (pinfunction "1_1") (pintype "bidirectional"))
      (node (ref "U$1") (pin "13") (pinfunction "RADIO_A_EN_13") (pintype "bidirectional"))
    )
    (net (code "53") (name "Net-(U$1-RADIO_A_MISO)") (class "Default")
      (node (ref "R32") (pin "2") (pinfunction "2_2") (pintype "bidirectional"))
      (node (ref "U$1") (pin "62") (pinfunction "RADIO_A_MISO_62") (pintype "bidirectional"))
    )
    (net (code "54") (name "Net-(U$1-RADIO_A_MOSI)") (class "Default")
      (node (ref "R31") (pin "2") (pinfunction "2_2") (pintype "bidirectional"))
      (node (ref "U$1") (pin "63") (pinfunction "RADIO_A_MOSI_63") (pintype "bidirectional"))
    )
    (net (code "55") (name "Net-(U$1-RADIO_A_SCK)") (class "Default")
      (node (ref "R33") (pin "2") (pinfunction "2_2") (pintype "bidirectional"))
      (node (ref "U$1") (pin "61") (pinfunction "RADIO_A_SCK_61") (pintype "bidirectional"))
    )
    (net (code "56") (name "Net-(U$1-RADIO_B_CS)") (class "Default")
      (node (ref "R40") (pin "2") (pinfunction "2_2") (pintype "bidirectional"))
      (node (ref "U$1") (pin "19") (pinfunction "RADIO_B_CS_19") (pintype "bidirectional"))
    )
    (net (code "57") (name "Net-(U$1-RADIO_B_EN)") (class "Default")
      (node (ref "R17") (pin "1") (pinfunction "1_1") (pintype "bidirectional"))
      (node (ref "U$1") (pin "28") (pinfunction "RADIO_B_EN_28") (pintype "bidirectional"))
    )
    (net (code "58") (name "Net-(U$1-RADIO_B_MISO)") (class "Default")
      (node (ref "R42") (pin "2") (pinfunction "2_2") (pintype "bidirectional"))
      (node (ref "U$1") (pin "21") (pinfunction "RADIO_B_MISO_21") (pintype "bidirectional"))
    )
    (net (code "59") (name "Net-(U$1-RADIO_B_MOSI)") (class "Default")
      (node (ref "R41") (pin "2") (pinfunction "2_2") (pintype "bidirectional"))
      (node (ref "U$1") (pin "20") (pinfunction "RADIO_B_MOSI_20") (pintype "bidirectional"))
    )
    (net (code "60") (name "Net-(U$1-RADIO_B_SCK)") (class "Default")
      (node (ref "R43") (pin "2") (pinfunction "2_2") (pintype "bidirectional"))
      (node (ref "U$1") (pin "22") (pinfunction "RADIO_B_SCK_22") (pintype "bidirectional"))
    )
    (net (code "61") (name "Net-(U$1-RADIO_RST)") (class "Default")
      (node (ref "U$1") (pin "25") (pinfunction "RADIO_RST_25") (pintype "bidirectional"))
      (node (ref "U$2") (pin "9") (pinfunction "RST_9") (pintype "bidirectional"))
      (node (ref "U$3") (pin "9") (pinfunction "RST_9") (pintype "bidirectional"))
    )
    (net (code "62") (name "Net-(U$1-RESET)") (class "Default")
      (node (ref "J1") (pin "6") (pinfunction "6_6") (pintype "passive"))
      (node (ref "U$1") (pin "1") (pinfunction "RESET_1") (pintype "bidirectional"))
    )
    (net (code "63") (name "Net-(U$1-SCANMODE)") (class "Default")
      (node (ref "R10") (pin "2") (pinfunction "2_2") (pintype "bidirectional"))
      (node (ref "U$1") (pin "6") (pinfunction "SCANMODE_6") (pintype "bidirectional"))
    )
    (net (code "64") (name "Net-(U$1-SP_CLK_OUT)") (class "Default")
      (node (ref "R16") (pin "1") (pinfunction "1_1") (pintype "bidirectional"))
      (node (ref "U$1") (pin "39") (pinfunction "SP_CLK_OUT_39") (pintype "bidirectional"))
    )
    (net (code "65") (name "Net-(U$1-SP_VALID)") (class "Default")
      (node (ref "R9") (pin "2") (pinfunction "2_2") (pintype "bidirectional"))
      (node (ref "U$1") (pin "34") (pinfunction "SP_VALID_34") (pintype "bidirectional"))
    )
    (net (code "66") (name "Net-(U$2-CLK_IN)") (class "Default")
      (node (ref "R16") (pin "2") (pinfunction "2_2") (pintype "bidirectional"))
      (node (ref "U$2") (pin "11") (pinfunction "CLK_IN_11") (pintype "bidirectional"))
    )
    (net (code "67") (name "Net-(U$2-DIO0)") (class "Default")
      (node (ref "R29") (pin "1") (pinfunction "1_1") (pintype "bidirectional"))
      (node (ref "U$2") (pin "21") (pinfunction "DIO0_21") (pintype "bidirectional"))
    )
    (net (code "68") (name "Net-(U$2-DIO1)") (class "Default")
      (node (ref "R28") (pin "1") (pinfunction "1_1") (pintype "bidirectional"))
      (node (ref "U$2") (pin "22") (pinfunction "DIO1_22") (pintype "bidirectional"))
    )
    (net (code "69") (name "Net-(U$2-DIO2)") (class "Default")
      (node (ref "R27") (pin "1") (pinfunction "1_1") (pintype "bidirectional"))
      (node (ref "U$2") (pin "23") (pinfunction "DIO2_23") (pintype "bidirectional"))
    )
    (net (code "70") (name "Net-(U$2-DIO3)") (class "Default")
      (node (ref "R26") (pin "1") (pinfunction "1_1") (pintype "bidirectional"))
      (node (ref "U$2") (pin "24") (pinfunction "DIO3_24") (pintype "bidirectional"))
    )
    (net (code "71") (name "Net-(U$2-I_IN)") (class "Default")
      (node (ref "R7") (pin "1") (pinfunction "1_1") (pintype "bidirectional"))
      (node (ref "U$2") (pin "13") (pinfunction "I_IN_13") (pintype "bidirectional"))
    )
    (net (code "72") (name "Net-(U$2-I_OUT)") (class "Default")
      (node (ref "R34") (pin "1") (pinfunction "1_1") (pintype "bidirectional"))
      (node (ref "U$2") (pin "15") (pinfunction "I_OUT_15") (pintype "bidirectional"))
    )
    (net (code "73") (name "Net-(U$2-MISO)") (class "Default")
      (node (ref "R32") (pin "1") (pinfunction "1_1") (pintype "bidirectional"))
      (node (ref "U$2") (pin "18") (pinfunction "MISO_18") (pintype "bidirectional"))
    )
    (net (code "74") (name "Net-(U$2-MOSI)") (class "Default")
      (node (ref "R31") (pin "1") (pinfunction "1_1") (pintype "bidirectional"))
      (node (ref "U$2") (pin "19") (pinfunction "MOSI_19") (pintype "bidirectional"))
    )
    (net (code "75") (name "Net-(U$2-NSS)") (class "Default")
      (node (ref "R30") (pin "1") (pinfunction "1_1") (pintype "bidirectional"))
      (node (ref "U$2") (pin "20") (pinfunction "NSS_20") (pintype "bidirectional"))
    )
    (net (code "76") (name "Net-(U$2-Q_IN)") (class "Default")
      (node (ref "R8") (pin "1") (pinfunction "1_1") (pintype "bidirectional"))
      (node (ref "U$2") (pin "12") (pinfunction "Q_IN_12") (pintype "bidirectional"))
    )
    (net (code "77") (name "Net-(U$2-Q_OUT)") (class "Default")
      (node (ref "R35") (pin "1") (pinfunction "1_1") (pintype "bidirectional"))
      (node (ref "U$2") (pin "14") (pinfunction "Q_OUT_14") (pintype "bidirectional"))
    )
    (net (code "78") (name "Net-(U$2-RF_IN)") (class "Default")
      (node (ref "L1") (pin "2") (pinfunction "2_2") (pintype "passive"))
      (node (ref "L2") (pin "1") (pinfunction "1_1") (pintype "passive"))
      (node (ref "U$2") (pin "27") (pinfunction "RF_IN_27") (pintype "bidirectional"))
    )
    (net (code "79") (name "Net-(U$2-RF_ON)") (class "Default")
      (node (ref "C25") (pin "2") (pinfunction "2_2") (pintype "passive"))
      (node (ref "C26") (pin "1") (pinfunction "1_1") (pintype "passive"))
      (node (ref "U$2") (pin "29") (pinfunction "RF_ON_29") (pintype "bidirectional"))
    )
    (net (code "80") (name "Net-(U$2-RF_OP)") (class "Default")
      (node (ref "C25") (pin "1") (pinfunction "1_1") (pintype "passive"))
      (node (ref "L3") (pin "1") (pinfunction "1_1") (pintype "passive"))
      (node (ref "U$2") (pin "30") (pinfunction "RF_OP_30") (pintype "bidirectional"))
    )
    (net (code "81") (name "Net-(U$2-SCK)") (class "Default")
      (node (ref "R33") (pin "1") (pinfunction "1_1") (pintype "bidirectional"))
      (node (ref "U$2") (pin "17") (pinfunction "SCK_17") (pintype "bidirectional"))
    )
    (net (code "82") (name "Net-(U$2-VR_ANA1)") (class "Default")
      (node (ref "C16") (pin "1") (pinfunction "1_1") (pintype "passive"))
      (node (ref "U$2") (pin "3") (pinfunction "VR_ANA1_3") (pintype "bidirectional"))
    )
    (net (code "83") (name "Net-(U$2-VR_ANA2)") (class "Default")
      (node (ref "C15") (pin "1") (pinfunction "1_1") (pintype "passive"))
      (node (ref "U$2") (pin "25") (pinfunction "VR_ANA2_25") (pintype "bidirectional"))
    )
    (net (code "84") (name "Net-(U$2-VR_DIG)") (class "Default")
      (node (ref "C17") (pin "1") (pinfunction "1_1") (pintype "passive"))
      (node (ref "U$2") (pin "5") (pinfunction "VR_DIG_5") (pintype "bidirectional"))
    )
    (net (code "85") (name "Net-(U$2-VR_PA)") (class "Default")
      (node (ref "C11") (pin "1") (pinfunction "1_1") (pintype "passive"))
      (node (ref "U$2") (pin "1") (pinfunction "VR_PA_1") (pintype "bidirectional"))
    )
    (net (code "86") (name "Net-(U$2-XTB)") (class "Default")
      (node (ref "C19") (pin "1") (pinfunction "1_1") (pintype "passive"))
      (node (ref "U$2") (pin "8") (pinfunction "XTB_8") (pintype "bidirectional"))
    )
    (net (code "87") (name "Net-(U$3-DIO0)") (class "Default")
      (node (ref "R39") (pin "1") (pinfunction "1_1") (pintype "bidirectional"))
      (node (ref "U$3") (pin "21") (pinfunction "DIO0_21") (pintype "bidirectional"))
    )
    (net (code "88") (name "Net-(U$3-DIO1)") (class "Default")
      (node (ref "R38") (pin "1") (pinfunction "1_1") (pintype "bidirectional"))
      (node (ref "U$3") (pin "22") (pinfunction "DIO1_22") (pintype "bidirectional"))
    )
    (net (code "89") (name "Net-(U$3-DIO2)") (class "Default")
      (node (ref "R37") (pin "1") (pinfunction "1_1") (pintype "bidirectional"))
      (node (ref "U$3") (pin "23") (pinfunction "DIO2_23") (pintype "bidirectional"))
    )
    (net (code "90") (name "Net-(U$3-DIO3)") (class "Default")
      (node (ref "R36") (pin "1") (pinfunction "1_1") (pintype "bidirectional"))
      (node (ref "U$3") (pin "24") (pinfunction "DIO3_24") (pintype "bidirectional"))
    )
    (net (code "91") (name "Net-(U$3-I_IN)") (class "Default")
      (node (ref "R3") (pin "1") (pinfunction "1_1") (pintype "bidirectional"))
      (node (ref "U$3") (pin "13") (pinfunction "I_IN_13") (pintype "bidirectional"))
    )
    (net (code "92") (name "Net-(U$3-I_OUT)") (class "Default")
      (node (ref "R44") (pin "1") (pinfunction "1_1") (pintype "bidirectional"))
      (node (ref "U$3") (pin "15") (pinfunction "I_OUT_15") (pintype "bidirectional"))
    )
    (net (code "93") (name "Net-(U$3-MISO)") (class "Default")
      (node (ref "R42") (pin "1") (pinfunction "1_1") (pintype "bidirectional"))
      (node (ref "U$3") (pin "18") (pinfunction "MISO_18") (pintype "bidirectional"))
    )
    (net (code "94") (name "Net-(U$3-MOSI)") (class "Default")
      (node (ref "R41") (pin "1") (pinfunction "1_1") (pintype "bidirectional"))
      (node (ref "U$3") (pin "19") (pinfunction "MOSI_19") (pintype "bidirectional"))
    )
    (net (code "95") (name "Net-(U$3-NSS)") (class "Default")
      (node (ref "R40") (pin "1") (pinfunction "1_1") (pintype "bidirectional"))
      (node (ref "U$3") (pin "20") (pinfunction "NSS_20") (pintype "bidirectional"))
    )
    (net (code "96") (name "Net-(U$3-Q_IN)") (class "Default")
      (node (ref "R4") (pin "1") (pinfunction "1_1") (pintype "bidirectional"))
      (node (ref "U$3") (pin "12") (pinfunction "Q_IN_12") (pintype "bidirectional"))
    )
    (net (code "97") (name "Net-(U$3-Q_OUT)") (class "Default")
      (node (ref "R45") (pin "1") (pinfunction "1_1") (pintype "bidirectional"))
      (node (ref "U$3") (pin "14") (pinfunction "Q_OUT_14") (pintype "bidirectional"))
    )
    (net (code "98") (name "Net-(U$3-RF_IN)") (class "Default")
      (node (ref "L4") (pin "2") (pinfunction "2_2") (pintype "passive"))
      (node (ref "L5") (pin "1") (pinfunction "1_1") (pintype "passive"))
      (node (ref "U$3") (pin "27") (pinfunction "RF_IN_27") (pintype "bidirectional"))
    )
    (net (code "99") (name "Net-(U$3-RF_ON)") (class "Default")
      (node (ref "C40") (pin "2") (pinfunction "2_2") (pintype "passive"))
      (node (ref "C41") (pin "1") (pinfunction "1_1") (pintype "passive"))
      (node (ref "U$3") (pin "29") (pinfunction "RF_ON_29") (pintype "bidirectional"))
    )
    (net (code "100") (name "Net-(U$3-RF_OP)") (class "Default")
      (node (ref "C40") (pin "1") (pinfunction "1_1") (pintype "passive"))
      (node (ref "L6") (pin "1") (pinfunction "1_1") (pintype "passive"))
      (node (ref "U$3") (pin "30") (pinfunction "RF_OP_30") (pintype "bidirectional"))
    )
    (net (code "101") (name "Net-(U$3-SCK)") (class "Default")
      (node (ref "R43") (pin "1") (pinfunction "1_1") (pintype "bidirectional"))
      (node (ref "U$3") (pin "17") (pinfunction "SCK_17") (pintype "bidirectional"))
    )
    (net (code "102") (name "Net-(U$3-VR_ANA1)") (class "Default")
      (node (ref "C32") (pin "1") (pinfunction "1_1") (pintype "passive"))
      (node (ref "U$3") (pin "3") (pinfunction "VR_ANA1_3") (pintype "bidirectional"))
    )
    (net (code "103") (name "Net-(U$3-VR_ANA2)") (class "Default")
      (node (ref "C31") (pin "1") (pinfunction "1_1") (pintype "passive"))
      (node (ref "U$3") (pin "25") (pinfunction "VR_ANA2_25") (pintype "bidirectional"))
    )
    (net (code "104") (name "Net-(U$3-VR_DIG)") (class "Default")
      (node (ref "C33") (pin "1") (pinfunction "1_1") (pintype "passive"))
      (node (ref "U$3") (pin "5") (pinfunction "VR_DIG_5") (pintype "bidirectional"))
    )
    (net (code "105") (name "Net-(U$3-VR_PA)") (class "Default")
      (node (ref "C27") (pin "1") (pinfunction "1_1") (pintype "passive"))
      (node (ref "U$3") (pin "1") (pinfunction "VR_PA_1") (pintype "bidirectional"))
    )
    (net (code "106") (name "Net-(U$3-XTB)") (class "Default")
      (node (ref "C34") (pin "1") (pinfunction "1_1") (pintype "passive"))
      (node (ref "U$3") (pin "8") (pinfunction "XTB_8") (pintype "bidirectional"))
    )
    (net (code "107") (name "Net-(U1-EN)") (class "Default")
      (node (ref "R22") (pin "2") (pinfunction "2_2") (pintype "bidirectional"))
      (node (ref "U1") (pin "1") (pinfunction "EN_1") (pintype "bidirectional"))
    )
    (net (code "108") (name "Net-(U1-OUT)") (class "Default")
      (node (ref "R21") (pin "1") (pinfunction "1_1") (pintype "bidirectional"))
      (node (ref "U1") (pin "3") (pinfunction "OUT_3") (pintype "bidirectional"))
    )
    (net (code "109") (name "Net-(U1-VCC)") (class "Default")
      (node (ref "C10") (pin "1") (pinfunction "1_1") (pintype "passive"))
      (node (ref "R22") (pin "1") (pinfunction "1_1") (pintype "bidirectional"))
      (node (ref "R23") (pin "2") (pinfunction "2_2") (pintype "bidirectional"))
      (node (ref "U1") (pin "4") (pinfunction "VCC_4") (pintype "bidirectional"))
    )
    (net (code "110") (name "Net-(U2-EN)") (class "Default")
      (node (ref "R24") (pin "2") (pinfunction "2_2") (pintype "bidirectional"))
      (node (ref "U2") (pin "1") (pinfunction "EN_1") (pintype "bidirectional"))
    )
    (net (code "111") (name "Net-(U2-OUT)") (class "Default")
      (node (ref "C19") (pin "2") (pinfunction "2_2") (pintype "passive"))
      (node (ref "C34") (pin "2") (pinfunction "2_2") (pintype "passive"))
      (node (ref "U2") (pin "3") (pinfunction "OUT_3") (pintype "bidirectional"))
    )
    (net (code "112") (name "Net-(U2-VCC)") (class "Default")
      (node (ref "C18") (pin "1") (pinfunction "1_1") (pintype "passive"))
      (node (ref "R24") (pin "1") (pinfunction "1_1") (pintype "bidirectional"))
      (node (ref "R25") (pin "2") (pinfunction "2_2") (pintype "bidirectional"))
      (node (ref "U2") (pin "4") (pinfunction "VCC_4") (pintype "bidirectional"))
    )
    (net (code "113") (name "unconnected-(R1-Pad2)") (class "Default")
      (node (ref "R1") (pin "2") (pinfunction "2_2") (pintype "bidirectional"))
    )
    (net (code "114") (name "unconnected-(R2-Pad2)") (class "Default")
      (node (ref "R2") (pin "2") (pinfunction "2_2") (pintype "bidirectional"))
    )
    (net (code "115") (name "unconnected-(R5-Pad2)") (class "Default")
      (node (ref "R5") (pin "2") (pinfunction "2_2") (pintype "bidirectional"))
    )
    (net (code "116") (name "unconnected-(R17-Pad2)") (class "Default")
      (node (ref "R17") (pin "2") (pinfunction "2_2") (pintype "bidirectional"))
    )
    (net (code "117") (name "unconnected-(R18-Pad2)") (class "Default")
      (node (ref "R18") (pin "2") (pinfunction "2_2") (pintype "bidirectional"))
    )
    (net (code "118") (name "unconnected-(R19-Pad2)") (class "Default")
      (node (ref "R19") (pin "2") (pinfunction "2_2") (pintype "bidirectional"))
    )
    (net (code "119") (name "unconnected-(U$1-PA_GAIN0-Pad18)") (class "Default")
      (node (ref "U$1") (pin "18") (pinfunction "PA_GAIN0_18") (pintype "bidirectional"))
    )
    (net (code "120") (name "unconnected-(U$1-PA_GAIN1-Pad17)") (class "Default")
      (node (ref "U$1") (pin "17") (pinfunction "PA_GAIN1_17") (pintype "bidirectional"))
    )
    (net (code "121") (name "unconnected-(U$2-XTA-Pad6)") (class "Default")
      (node (ref "U$2") (pin "6") (pinfunction "XTA_6") (pintype "bidirectional"))
    )
    (net (code "122") (name "unconnected-(U$3-CLK_IN-Pad11)") (class "Default")
      (node (ref "U$3") (pin "11") (pinfunction "CLK_IN_11") (pintype "bidirectional"))
    )
    (net (code "123") (name "unconnected-(U$3-XTA-Pad6)") (class "Default")
      (node (ref "U$3") (pin "6") (pinfunction "XTA_6") (pintype "bidirectional"))
    )
  )
)
